# 1_-MCU_LPC1777.net
KiCad netlist of a schematic drawn in Altium Designer
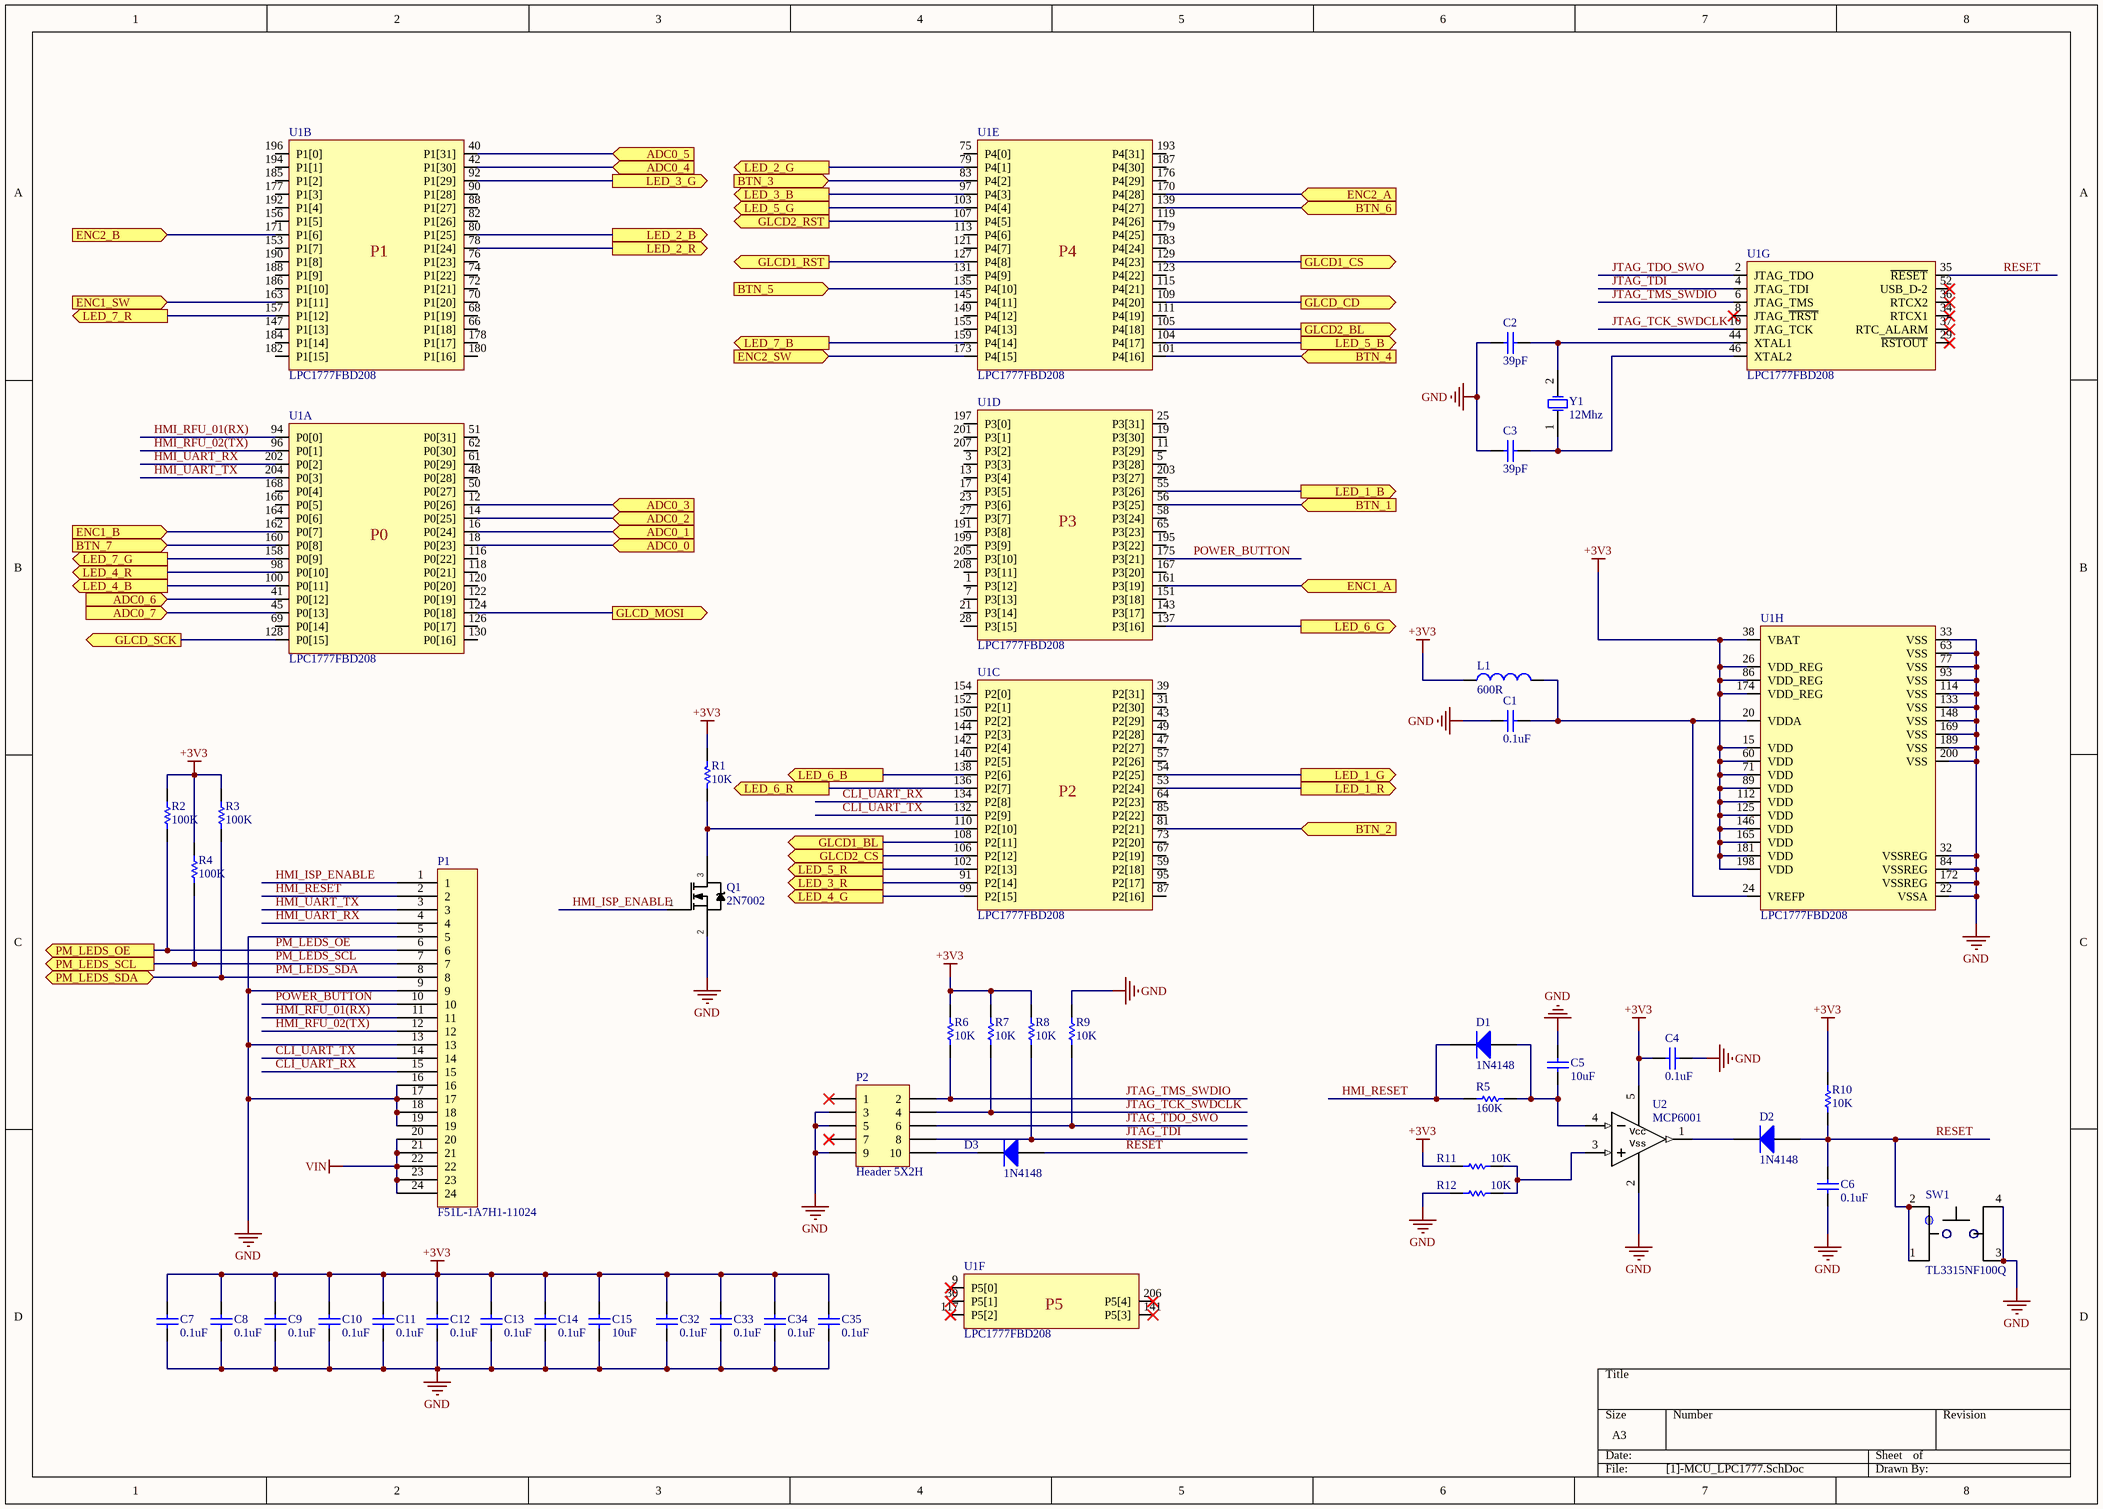
[diagram p0: [1]-MCU_LPC1777.SchDoc]

(export (version "E")
  (design (tool "Eeschema 10.0.6"))
  (components
    (comp (ref "C1")
      (value "0.1uF")
      (footprint "CAPC1005N")
      (description "CAP CER 0.1UF 50V X7R 0402")
      (fields (field (name "TOLERANCE") "10 %"))
      (libsource (lib "bitsnio") (part "GRM155R71H104KE14D"))
    )
    (comp (ref "C2")
      (value "39pF")
      (footprint "CAPC1608N")
      (description "CAP CER 39PF 50V NP0 0603")
      (fields (field (name "TOLERANCE") "5%"))
      (libsource (lib "bitsnio") (part "C1608NP01H390J080AA"))
    )
    (comp (ref "C3")
      (value "39pF")
      (footprint "CAPC1608N")
      (description "CAP CER 39PF 50V NP0 0603")
      (fields (field (name "TOLERANCE") "5%"))
      (libsource (lib "bitsnio") (part "C1608NP01H390J080AA"))
    )
    (comp (ref "C4")
      (value "0.1uF")
      (footprint "CAPC1608N")
      (description "CAP CER 0.1UF 25V X7R 0603")
      (fields (field (name "TOLERANCE") "10%") (field (name "VOLTAGE") "25V"))
      (libsource (lib "bitsnio") (part "CC0603KRX7R8BB104"))
    )
    (comp (ref "C5")
      (value "10uF")
      (footprint "CAPC1608N")
      (description "CAP CER 10UF 10V X5R 0603")
      (fields (field (name "TOLERANCE") "10%") (field (name "VOLTAGE") "10V"))
      (libsource (lib "bitsnio") (part "GRM188R61A106KE69D"))
    )
    (comp (ref "C6")
      (value "0.1uF")
      (footprint "CAPC1608N")
      (description "CAP CER 0.1UF 25V X7R 0603")
      (fields (field (name "TOLERANCE") "10%") (field (name "VOLTAGE") "25V"))
      (libsource (lib "bitsnio") (part "CC0603KRX7R8BB104"))
    )
    (comp (ref "C7")
      (value "0.1uF")
      (footprint "CAPC1005N")
      (description "CAP CER 0.1UF 50V X7R 0402")
      (fields (field (name "TOLERANCE") "10 %"))
      (libsource (lib "bitsnio") (part "GRM155R71H104KE14D"))
    )
    (comp (ref "C8")
      (value "0.1uF")
      (footprint "CAPC1005N")
      (description "CAP CER 0.1UF 50V X7R 0402")
      (fields (field (name "TOLERANCE") "10 %"))
      (libsource (lib "bitsnio") (part "GRM155R71H104KE14D"))
    )
    (comp (ref "C9")
      (value "0.1uF")
      (footprint "CAPC1005N")
      (description "CAP CER 0.1UF 50V X7R 0402")
      (fields (field (name "TOLERANCE") "10 %"))
      (libsource (lib "bitsnio") (part "GRM155R71H104KE14D"))
    )
    (comp (ref "C10")
      (value "0.1uF")
      (footprint "CAPC1005N")
      (description "CAP CER 0.1UF 50V X7R 0402")
      (fields (field (name "TOLERANCE") "10 %"))
      (libsource (lib "bitsnio") (part "GRM155R71H104KE14D"))
    )
    (comp (ref "C11")
      (value "0.1uF")
      (footprint "CAPC1005N")
      (description "CAP CER 0.1UF 50V X7R 0402")
      (fields (field (name "TOLERANCE") "10 %"))
      (libsource (lib "bitsnio") (part "GRM155R71H104KE14D"))
    )
    (comp (ref "C12")
      (value "0.1uF")
      (footprint "CAPC1005N")
      (description "CAP CER 0.1UF 50V X7R 0402")
      (fields (field (name "TOLERANCE") "10 %"))
      (libsource (lib "bitsnio") (part "GRM155R71H104KE14D"))
    )
    (comp (ref "C13")
      (value "0.1uF")
      (footprint "CAPC1005N")
      (description "CAP CER 0.1UF 50V X7R 0402")
      (fields (field (name "TOLERANCE") "10 %"))
      (libsource (lib "bitsnio") (part "GRM155R71H104KE14D"))
    )
    (comp (ref "C14")
      (value "0.1uF")
      (footprint "CAPC1005N")
      (description "CAP CER 0.1UF 50V X7R 0402")
      (fields (field (name "TOLERANCE") "10 %"))
      (libsource (lib "bitsnio") (part "GRM155R71H104KE14D"))
    )
    (comp (ref "C15")
      (value "10uF")
      (footprint "CAPC1608N")
      (description "CAP CER 10UF 10V X5R 0603")
      (fields (field (name "TOLERANCE") "10%") (field (name "VOLTAGE") "10V"))
      (libsource (lib "bitsnio") (part "GRM188R61A106KE69D"))
    )
    (comp (ref "C32")
      (value "0.1uF")
      (footprint "CAPC1005N")
      (description "CAP CER 0.1UF 50V X7R 0402")
      (fields (field (name "TOLERANCE") "10 %"))
      (libsource (lib "bitsnio") (part "GRM155R71H104KE14D"))
    )
    (comp (ref "C33")
      (value "0.1uF")
      (footprint "CAPC1005N")
      (description "CAP CER 0.1UF 50V X7R 0402")
      (fields (field (name "TOLERANCE") "10 %"))
      (libsource (lib "bitsnio") (part "GRM155R71H104KE14D"))
    )
    (comp (ref "C34")
      (value "0.1uF")
      (footprint "CAPC1005N")
      (description "CAP CER 0.1UF 50V X7R 0402")
      (fields (field (name "TOLERANCE") "10 %"))
      (libsource (lib "bitsnio") (part "GRM155R71H104KE14D"))
    )
    (comp (ref "C35")
      (value "0.1uF")
      (footprint "CAPC1005N")
      (description "CAP CER 0.1UF 50V X7R 0402")
      (fields (field (name "TOLERANCE") "10 %"))
      (libsource (lib "bitsnio") (part "GRM155R71H104KE14D"))
    )
    (comp (ref "D1")
      (value "1N4148")
      (footprint "SOD-323")
      (description "DIODE SWITCHING 75V 0.15A SOD323")
      (fields (field (name "VOLTAGE") "75V"))
      (libsource (lib "bitsnio") (part "1N4148WS-7-F"))
    )
    (comp (ref "D2")
      (value "1N4148")
      (footprint "SOD-323")
      (description "DIODE SWITCHING 75V 0.15A SOD323")
      (fields (field (name "VOLTAGE") "75V"))
      (libsource (lib "bitsnio") (part "1N4148WS-7-F"))
    )
    (comp (ref "D3")
      (value "1N4148")
      (footprint "SOD-323")
      (description "DIODE SWITCHING 75V 0.15A SOD323")
      (fields (field (name "VOLTAGE") "75V"))
      (libsource (lib "bitsnio") (part "1N4148WS-7-F"))
    )
    (comp (ref "L1")
      (value "600R")
      (footprint "INDC1608N")
      (description "FERRITE BEAD 600 OHM 1.0A 0603")
      (fields (field (name "TOLERANCE") "25%"))
      (libsource (lib "bitsnio") (part "742792651"))
    )
    (comp (ref "P1")
      (value "F51L-1A7H1-11024")
      (footprint "F51L-1A7H1-11024")
      (description "FLEX CONNECTOR, 1.00MM PITCH, HE")
      (libsource (lib "bitsnio") (part "F51L-1A7H1-11024"))
    )
    (comp (ref "P2")
      (value "Header 5X2H")
      (footprint "HDR2x5_1P27")
      (description "Header, 5-Pin, Dual row, Right Angle")
      (fields (field (name "PUBLISHER") "Altium Limited"))
      (libsource (lib "Miscellaneous Connectors") (part "Header 5X2H"))
    )
    (comp (ref "Q1")
      (value "2N7002")
      (footprint "SOT23-3N")
      (description "MOSFET N-CH 60V 115MA SOT-23")
      (fields (field (name "VOLTAGE") "60V"))
      (libsource (lib "bitsnio") (part "2N7002"))
    )
    (comp (ref "R1")
      (value "10K")
      (footprint "RESC1608N")
      (description "RES SMD 10K OHM 5% 1/10W 0603")
      (fields (field (name "TOLERANCE") "5%"))
      (libsource (lib "bitsnio") (part "AC0603JR-0710KL"))
    )
    (comp (ref "R2")
      (value "100K")
      (footprint "RESC1608N")
      (description "RES SMD 100K OHM 5% 1/4W 0603")
      (fields (field (name "TOLERANCE") "5%"))
      (libsource (lib "bitsnio") (part "ESR03EZPJ104"))
    )
    (comp (ref "R3")
      (value "100K")
      (footprint "RESC1608N")
      (description "RES SMD 100K OHM 5% 1/4W 0603")
      (fields (field (name "TOLERANCE") "5%"))
      (libsource (lib "bitsnio") (part "ESR03EZPJ104"))
    )
    (comp (ref "R4")
      (value "100K")
      (footprint "RESC1608N")
      (description "RES SMD 100K OHM 5% 1/4W 0603")
      (fields (field (name "TOLERANCE") "5%"))
      (libsource (lib "bitsnio") (part "ESR03EZPJ104"))
    )
    (comp (ref "R5")
      (value "160K")
      (footprint "RESC1608N")
      (description "RES SMD 160K OHM 5% 1/10W 0603")
      (fields (field (name "TOLERANCE") "5%"))
      (libsource (lib "bitsnio") (part "RMCF0603JT160K"))
    )
    (comp (ref "R6")
      (value "10K")
      (footprint "RESC1608N")
      (description "RES SMD 10K OHM 5% 1/10W 0603")
      (fields (field (name "TOLERANCE") "5%"))
      (libsource (lib "bitsnio") (part "AC0603JR-0710KL"))
    )
    (comp (ref "R7")
      (value "10K")
      (footprint "RESC1608N")
      (description "RES SMD 10K OHM 5% 1/10W 0603")
      (fields (field (name "TOLERANCE") "5%"))
      (libsource (lib "bitsnio") (part "AC0603JR-0710KL"))
    )
    (comp (ref "R8")
      (value "10K")
      (footprint "RESC1608N")
      (description "RES SMD 10K OHM 5% 1/10W 0603")
      (fields (field (name "TOLERANCE") "5%"))
      (libsource (lib "bitsnio") (part "AC0603JR-0710KL"))
    )
    (comp (ref "R9")
      (value "10K")
      (footprint "RESC1608N")
      (description "RES SMD 10K OHM 5% 1/10W 0603")
      (fields (field (name "TOLERANCE") "5%"))
      (libsource (lib "bitsnio") (part "AC0603JR-0710KL"))
    )
    (comp (ref "R10")
      (value "10K")
      (footprint "RESC1608N")
      (description "RES SMD 10K OHM 5% 1/10W 0603")
      (fields (field (name "TOLERANCE") "5%"))
      (libsource (lib "bitsnio") (part "AC0603JR-0710KL"))
    )
    (comp (ref "R11")
      (value "10K")
      (footprint "RESC1608N")
      (description "RES SMD 10K OHM 5% 1/10W 0603")
      (fields (field (name "TOLERANCE") "5%"))
      (libsource (lib "bitsnio") (part "AC0603JR-0710KL"))
    )
    (comp (ref "R12")
      (value "10K")
      (footprint "RESC1608N")
      (description "RES SMD 10K OHM 5% 1/10W 0603")
      (fields (field (name "TOLERANCE") "5%"))
      (libsource (lib "bitsnio") (part "AC0603JR-0710KL"))
    )
    (comp (ref "SW1")
      (value "TL3315NF100Q")
      (footprint "TL3315")
      (description "SWITCH TACTILE SPST-NO 0.05A 15V")
      (libsource (lib "bitsnio") (part "TL3315NF100Q"))
    )
    (comp (ref "U1")
      (value "LPC1777FBD208")
      (footprint "LQFP-208")
      (description "IC MCU 32BIT 512KB FLASH 208LQFP")
      (libsource (lib "bitsnio") (part "IC_LPC1777FBD208,551"))
    )
    (comp (ref "U2")
      (value "MCP6001")
      (footprint "SOT23-5N")
      (description "IC OPAMP GP 1MHZ RRO SOT23-5")
      (fields (field (name "VOLTAGE") "6V"))
      (libsource (lib "bitsnio") (part "IC_MCP6001T-I/OT"))
    )
    (comp (ref "Y1")
      (value "12Mhz")
      (footprint "CRYSTAL_HC49SDLF")
      (description "CRYSTAL 12.0000MHZ 20PF SMD")
      (libsource (lib "bitsnio") (part "FC4SDCBMF12.0-T1"))
    )
  )
  (nets
    (net (code "1") (name "+3V3") (class "Default")
      (node (ref "C10") (pin "2") (pinfunction "2_2") (pintype "passive"))
      (node (ref "C11") (pin "2") (pinfunction "2_2") (pintype "passive"))
      (node (ref "C12") (pin "2") (pinfunction "2_2") (pintype "passive"))
      (node (ref "C13") (pin "2") (pinfunction "2_2") (pintype "passive"))
      (node (ref "C14") (pin "2") (pinfunction "2_2") (pintype "passive"))
      (node (ref "C15") (pin "2") (pinfunction "2_2") (pintype "passive"))
      (node (ref "C32") (pin "2") (pinfunction "2_2") (pintype "passive"))
      (node (ref "C33") (pin "2") (pinfunction "2_2") (pintype "passive"))
      (node (ref "C34") (pin "2") (pinfunction "2_2") (pintype "passive"))
      (node (ref "C35") (pin "2") (pinfunction "2_2") (pintype "passive"))
      (node (ref "C4") (pin "2") (pinfunction "2_2") (pintype "passive"))
      (node (ref "C7") (pin "2") (pinfunction "2_2") (pintype "passive"))
      (node (ref "C8") (pin "2") (pinfunction "2_2") (pintype "passive"))
      (node (ref "C9") (pin "2") (pinfunction "2_2") (pintype "passive"))
      (node (ref "L1") (pin "2") (pinfunction "2_2") (pintype "passive"))
      (node (ref "R1") (pin "1") (pinfunction "1_1") (pintype "passive"))
      (node (ref "R10") (pin "1") (pinfunction "1_1") (pintype "passive"))
      (node (ref "R11") (pin "2") (pinfunction "2_2") (pintype "passive"))
      (node (ref "R2") (pin "2") (pinfunction "2_2") (pintype "passive"))
      (node (ref "R3") (pin "2") (pinfunction "2_2") (pintype "passive"))
      (node (ref "R4") (pin "2") (pinfunction "2_2") (pintype "passive"))
      (node (ref "R6") (pin "1") (pinfunction "1_1") (pintype "passive"))
      (node (ref "R7") (pin "1") (pinfunction "1_1") (pintype "passive"))
      (node (ref "R8") (pin "1") (pinfunction "1_1") (pintype "passive"))
      (node (ref "U1") (pin "112") (pinfunction "VDD_112") (pintype "passive"))
      (node (ref "U1") (pin "125") (pinfunction "VDD_125") (pintype "passive"))
      (node (ref "U1") (pin "146") (pinfunction "VDD_146") (pintype "passive"))
      (node (ref "U1") (pin "15") (pinfunction "VDD_15") (pintype "passive"))
      (node (ref "U1") (pin "165") (pinfunction "VDD_165") (pintype "passive"))
      (node (ref "U1") (pin "174") (pinfunction "VDD_REG_174") (pintype "passive"))
      (node (ref "U1") (pin "181") (pinfunction "VDD_181") (pintype "passive"))
      (node (ref "U1") (pin "198") (pinfunction "VDD_198") (pintype "passive"))
      (node (ref "U1") (pin "26") (pinfunction "VDD_REG_26") (pintype "passive"))
      (node (ref "U1") (pin "38") (pinfunction "VBAT_38") (pintype "passive"))
      (node (ref "U1") (pin "60") (pinfunction "VDD_60") (pintype "passive"))
      (node (ref "U1") (pin "71") (pinfunction "VDD_71") (pintype "passive"))
      (node (ref "U1") (pin "86") (pinfunction "VDD_REG_86") (pintype "passive"))
      (node (ref "U1") (pin "89") (pinfunction "VDD_89") (pintype "passive"))
      (node (ref "U2") (pin "5") (pinfunction "VCC_5") (pintype "power_in"))
    )
    (net (code "2") (name "/ADC0_0") (class "Default")
      (node (ref "U1") (pin "18") (pinfunction "P0[23]_18") (pintype "passive"))
    )
    (net (code "3") (name "/ADC0_1") (class "Default")
      (node (ref "U1") (pin "16") (pinfunction "P0[24]_16") (pintype "passive"))
    )
    (net (code "4") (name "/ADC0_2") (class "Default")
      (node (ref "U1") (pin "14") (pinfunction "P0[25]_14") (pintype "passive"))
    )
    (net (code "5") (name "/ADC0_3") (class "Default")
      (node (ref "U1") (pin "12") (pinfunction "P0[26]_12") (pintype "passive"))
    )
    (net (code "6") (name "/ADC0_4") (class "Default")
      (node (ref "U1") (pin "42") (pinfunction "P1[30]_42") (pintype "passive"))
    )
    (net (code "7") (name "/ADC0_5") (class "Default")
      (node (ref "U1") (pin "40") (pinfunction "P1[31]_40") (pintype "passive"))
    )
    (net (code "8") (name "/ADC0_6") (class "Default")
      (node (ref "U1") (pin "41") (pinfunction "P0[12]_41") (pintype "passive"))
    )
    (net (code "9") (name "/ADC0_7") (class "Default")
      (node (ref "U1") (pin "45") (pinfunction "P0[13]_45") (pintype "passive"))
    )
    (net (code "10") (name "/BTN_1") (class "Default")
      (node (ref "U1") (pin "56") (pinfunction "P3[25]_56") (pintype "passive"))
    )
    (net (code "11") (name "/BTN_2") (class "Default")
      (node (ref "U1") (pin "81") (pinfunction "P2[21]_81") (pintype "passive"))
    )
    (net (code "12") (name "/BTN_3") (class "Default")
      (node (ref "U1") (pin "83") (pinfunction "P4[2]_83") (pintype "passive"))
    )
    (net (code "13") (name "/BTN_4") (class "Default")
      (node (ref "U1") (pin "101") (pinfunction "P4[16]_101") (pintype "passive"))
    )
    (net (code "14") (name "/BTN_5") (class "Default")
      (node (ref "U1") (pin "135") (pinfunction "P4[10]_135") (pintype "passive"))
    )
    (net (code "15") (name "/BTN_6") (class "Default")
      (node (ref "U1") (pin "139") (pinfunction "P4[27]_139") (pintype "passive"))
    )
    (net (code "16") (name "/BTN_7") (class "Default")
      (node (ref "U1") (pin "160") (pinfunction "P0[8]_160") (pintype "passive"))
    )
    (net (code "17") (name "/CLI_UART_RX") (class "Default")
      (node (ref "P1") (pin "15") (pinfunction "15_15") (pintype "passive"))
      (node (ref "U1") (pin "134") (pinfunction "P2[8]_134") (pintype "passive"))
    )
    (net (code "18") (name "/CLI_UART_TX") (class "Default")
      (node (ref "P1") (pin "14") (pinfunction "14_14") (pintype "passive"))
      (node (ref "U1") (pin "132") (pinfunction "P2[9]_132") (pintype "passive"))
    )
    (net (code "19") (name "/ENC1_A") (class "Default")
      (node (ref "U1") (pin "161") (pinfunction "P3[19]_161") (pintype "passive"))
    )
    (net (code "20") (name "/ENC1_B") (class "Default")
      (node (ref "U1") (pin "162") (pinfunction "P0[7]_162") (pintype "passive"))
    )
    (net (code "21") (name "/ENC1_SW") (class "Default")
      (node (ref "U1") (pin "163") (pinfunction "P1[11]_163") (pintype "passive"))
    )
    (net (code "22") (name "/ENC2_A") (class "Default")
      (node (ref "U1") (pin "170") (pinfunction "P4[28]_170") (pintype "passive"))
    )
    (net (code "23") (name "/ENC2_B") (class "Default")
      (node (ref "U1") (pin "171") (pinfunction "P1[6]_171") (pintype "passive"))
    )
    (net (code "24") (name "/ENC2_SW") (class "Default")
      (node (ref "U1") (pin "173") (pinfunction "P4[15]_173") (pintype "passive"))
    )
    (net (code "25") (name "/GLCD1_BL") (class "Default")
      (node (ref "U1") (pin "108") (pinfunction "P2[11]_108") (pintype "passive"))
    )
    (net (code "26") (name "/GLCD1_CS") (class "Default")
      (node (ref "U1") (pin "129") (pinfunction "P4[23]_129") (pintype "passive"))
    )
    (net (code "27") (name "/GLCD1_RST") (class "Default")
      (node (ref "U1") (pin "127") (pinfunction "P4[8]_127") (pintype "passive"))
    )
    (net (code "28") (name "/GLCD2_BL") (class "Default")
      (node (ref "U1") (pin "105") (pinfunction "P4[18]_105") (pintype "passive"))
    )
    (net (code "29") (name "/GLCD2_CS") (class "Default")
      (node (ref "U1") (pin "106") (pinfunction "P2[12]_106") (pintype "passive"))
    )
    (net (code "30") (name "/GLCD2_RST") (class "Default")
      (node (ref "U1") (pin "107") (pinfunction "P4[5]_107") (pintype "passive"))
    )
    (net (code "31") (name "/GLCD_CD") (class "Default")
      (node (ref "U1") (pin "109") (pinfunction "P4[20]_109") (pintype "passive"))
    )
    (net (code "32") (name "/GLCD_MOSI") (class "Default")
      (node (ref "U1") (pin "124") (pinfunction "P0[18]_124") (pintype "passive"))
    )
    (net (code "33") (name "/GLCD_SCK") (class "Default")
      (node (ref "U1") (pin "128") (pinfunction "P0[15]_128") (pintype "passive"))
    )
    (net (code "34") (name "/HMI_ISP_ENABLE") (class "Default")
      (node (ref "P1") (pin "1") (pinfunction "1_1") (pintype "passive"))
      (node (ref "Q1") (pin "1") (pinfunction "G_1") (pintype "passive"))
    )
    (net (code "35") (name "/HMI_RESET") (class "Default")
      (node (ref "D1") (pin "1") (pinfunction "K_1") (pintype "passive"))
      (node (ref "P1") (pin "2") (pinfunction "2_2") (pintype "passive"))
      (node (ref "R5") (pin "1") (pinfunction "1_1") (pintype "passive"))
    )
    (net (code "36") (name "/HMI_RFU_01(RX)") (class "Default")
      (node (ref "P1") (pin "11") (pinfunction "11_11") (pintype "passive"))
      (node (ref "U1") (pin "94") (pinfunction "P0[0]_94") (pintype "passive"))
    )
    (net (code "37") (name "/HMI_RFU_02(TX)") (class "Default")
      (node (ref "P1") (pin "12") (pinfunction "12_12") (pintype "passive"))
      (node (ref "U1") (pin "96") (pinfunction "P0[1]_96") (pintype "passive"))
    )
    (net (code "38") (name "/HMI_UART_RX") (class "Default")
      (node (ref "P1") (pin "4") (pinfunction "4_4") (pintype "passive"))
      (node (ref "U1") (pin "202") (pinfunction "P0[2]_202") (pintype "passive"))
    )
    (net (code "39") (name "/HMI_UART_TX") (class "Default")
      (node (ref "P1") (pin "3") (pinfunction "3_3") (pintype "passive"))
      (node (ref "U1") (pin "204") (pinfunction "P0[3]_204") (pintype "passive"))
    )
    (net (code "40") (name "/JTAG_TCK_SWDCLK") (class "Default")
      (node (ref "P2") (pin "4") (pinfunction "4_4") (pintype "passive"))
      (node (ref "R7") (pin "2") (pinfunction "2_2") (pintype "passive"))
      (node (ref "U1") (pin "10") (pinfunction "JTAG_TCK_10") (pintype "passive"))
    )
    (net (code "41") (name "/JTAG_TDI") (class "Default")
      (node (ref "P2") (pin "8") (pinfunction "8_8") (pintype "passive"))
      (node (ref "R8") (pin "2") (pinfunction "2_2") (pintype "passive"))
      (node (ref "U1") (pin "4") (pinfunction "JTAG_TDI_4") (pintype "passive"))
    )
    (net (code "42") (name "/JTAG_TDO_SWO") (class "Default")
      (node (ref "P2") (pin "6") (pinfunction "6_6") (pintype "passive"))
      (node (ref "R9") (pin "2") (pinfunction "2_2") (pintype "passive"))
      (node (ref "U1") (pin "2") (pinfunction "JTAG_TDO_2") (pintype "passive"))
    )
    (net (code "43") (name "/JTAG_TMS_SWDIO") (class "Default")
      (node (ref "P2") (pin "2") (pinfunction "2_2") (pintype "passive"))
      (node (ref "R6") (pin "2") (pinfunction "2_2") (pintype "passive"))
      (node (ref "U1") (pin "6") (pinfunction "JTAG_TMS_6") (pintype "passive"))
    )
    (net (code "44") (name "/LED_1_B") (class "Default")
      (node (ref "U1") (pin "55") (pinfunction "P3[26]_55") (pintype "passive"))
    )
    (net (code "45") (name "/LED_1_G") (class "Default")
      (node (ref "U1") (pin "54") (pinfunction "P2[25]_54") (pintype "passive"))
    )
    (net (code "46") (name "/LED_1_R") (class "Default")
      (node (ref "U1") (pin "53") (pinfunction "P2[24]_53") (pintype "passive"))
    )
    (net (code "47") (name "/LED_2_B") (class "Default")
      (node (ref "U1") (pin "80") (pinfunction "P1[25]_80") (pintype "passive"))
    )
    (net (code "48") (name "/LED_2_G") (class "Default")
      (node (ref "U1") (pin "79") (pinfunction "P4[1]_79") (pintype "passive"))
    )
    (net (code "49") (name "/LED_2_R") (class "Default")
      (node (ref "U1") (pin "78") (pinfunction "P1[24]_78") (pintype "passive"))
    )
    (net (code "50") (name "/LED_3_B") (class "Default")
      (node (ref "U1") (pin "97") (pinfunction "P4[3]_97") (pintype "passive"))
    )
    (net (code "51") (name "/LED_3_G") (class "Default")
      (node (ref "U1") (pin "92") (pinfunction "P1[29]_92") (pintype "passive"))
    )
    (net (code "52") (name "/LED_3_R") (class "Default")
      (node (ref "U1") (pin "91") (pinfunction "P2[14]_91") (pintype "passive"))
    )
    (net (code "53") (name "/LED_4_B") (class "Default")
      (node (ref "U1") (pin "100") (pinfunction "P0[11]_100") (pintype "passive"))
    )
    (net (code "54") (name "/LED_4_G") (class "Default")
      (node (ref "U1") (pin "99") (pinfunction "P2[15]_99") (pintype "passive"))
    )
    (net (code "55") (name "/LED_4_R") (class "Default")
      (node (ref "U1") (pin "98") (pinfunction "P0[10]_98") (pintype "passive"))
    )
    (net (code "56") (name "/LED_5_B") (class "Default")
      (node (ref "U1") (pin "104") (pinfunction "P4[17]_104") (pintype "passive"))
    )
    (net (code "57") (name "/LED_5_G") (class "Default")
      (node (ref "U1") (pin "103") (pinfunction "P4[4]_103") (pintype "passive"))
    )
    (net (code "58") (name "/LED_5_R") (class "Default")
      (node (ref "U1") (pin "102") (pinfunction "P2[13]_102") (pintype "passive"))
    )
    (net (code "59") (name "/LED_6_B") (class "Default")
      (node (ref "U1") (pin "138") (pinfunction "P2[6]_138") (pintype "passive"))
    )
    (net (code "60") (name "/LED_6_G") (class "Default")
      (node (ref "U1") (pin "137") (pinfunction "P3[16]_137") (pintype "passive"))
    )
    (net (code "61") (name "/LED_6_R") (class "Default")
      (node (ref "U1") (pin "136") (pinfunction "P2[7]_136") (pintype "passive"))
    )
    (net (code "62") (name "/LED_7_B") (class "Default")
      (node (ref "U1") (pin "159") (pinfunction "P4[14]_159") (pintype "passive"))
    )
    (net (code "63") (name "/LED_7_G") (class "Default")
      (node (ref "U1") (pin "158") (pinfunction "P0[9]_158") (pintype "passive"))
    )
    (net (code "64") (name "/LED_7_R") (class "Default")
      (node (ref "U1") (pin "157") (pinfunction "P1[12]_157") (pintype "passive"))
    )
    (net (code "65") (name "/PM_LEDS_OE") (class "Default")
      (node (ref "P1") (pin "6") (pinfunction "6_6") (pintype "passive"))
      (node (ref "R2") (pin "1") (pinfunction "1_1") (pintype "passive"))
    )
    (net (code "66") (name "/PM_LEDS_SCL") (class "Default")
      (node (ref "P1") (pin "7") (pinfunction "7_7") (pintype "passive"))
      (node (ref "R4") (pin "1") (pinfunction "1_1") (pintype "passive"))
    )
    (net (code "67") (name "/PM_LEDS_SDA") (class "Default")
      (node (ref "P1") (pin "8") (pinfunction "8_8") (pintype "passive"))
      (node (ref "R3") (pin "1") (pinfunction "1_1") (pintype "passive"))
    )
    (net (code "68") (name "/POWER_BUTTON") (class "Default")
      (node (ref "P1") (pin "10") (pinfunction "10_10") (pintype "passive"))
      (node (ref "U1") (pin "175") (pinfunction "P3[21]_175") (pintype "passive"))
    )
    (net (code "69") (name "/RESET") (class "Default")
      (node (ref "C6") (pin "1") (pinfunction "1_1") (pintype "passive"))
      (node (ref "D2") (pin "2") (pinfunction "A_2") (pintype "passive"))
      (node (ref "D3") (pin "2") (pinfunction "A_2") (pintype "passive"))
      (node (ref "R10") (pin "2") (pinfunction "2_2") (pintype "passive"))
      (node (ref "SW1") (pin "1") (pinfunction "1_1") (pintype "passive"))
      (node (ref "SW1") (pin "2") (pinfunction "2_2") (pintype "passive"))
      (node (ref "U1") (pin "35") (pinfunction "~{RESET}_35") (pintype "passive"))
    )
    (net (code "70") (name "GND") (class "Default")
      (node (ref "C1") (pin "2") (pinfunction "2_2") (pintype "passive"))
      (node (ref "C10") (pin "1") (pinfunction "1_1") (pintype "passive"))
      (node (ref "C11") (pin "1") (pinfunction "1_1") (pintype "passive"))
      (node (ref "C12") (pin "1") (pinfunction "1_1") (pintype "passive"))
      (node (ref "C13") (pin "1") (pinfunction "1_1") (pintype "passive"))
      (node (ref "C14") (pin "1") (pinfunction "1_1") (pintype "passive"))
      (node (ref "C15") (pin "1") (pinfunction "1_1") (pintype "passive"))
      (node (ref "C2") (pin "2") (pinfunction "2_2") (pintype "passive"))
      (node (ref "C3") (pin "1") (pinfunction "1_1") (pintype "passive"))
      (node (ref "C32") (pin "1") (pinfunction "1_1") (pintype "passive"))
      (node (ref "C33") (pin "1") (pinfunction "1_1") (pintype "passive"))
      (node (ref "C34") (pin "1") (pinfunction "1_1") (pintype "passive"))
      (node (ref "C35") (pin "1") (pinfunction "1_1") (pintype "passive"))
      (node (ref "C4") (pin "1") (pinfunction "1_1") (pintype "passive"))
      (node (ref "C5") (pin "1") (pinfunction "1_1") (pintype "passive"))
      (node (ref "C6") (pin "2") (pinfunction "2_2") (pintype "passive"))
      (node (ref "C7") (pin "1") (pinfunction "1_1") (pintype "passive"))
      (node (ref "C8") (pin "1") (pinfunction "1_1") (pintype "passive"))
      (node (ref "C9") (pin "1") (pinfunction "1_1") (pintype "passive"))
      (node (ref "P1") (pin "13") (pinfunction "13_13") (pintype "passive"))
      (node (ref "P1") (pin "16") (pinfunction "16_16") (pintype "passive"))
      (node (ref "P1") (pin "17") (pinfunction "17_17") (pintype "passive"))
      (node (ref "P1") (pin "18") (pinfunction "18_18") (pintype "passive"))
      (node (ref "P1") (pin "19") (pinfunction "19_19") (pintype "passive"))
      (node (ref "P1") (pin "5") (pinfunction "5_5") (pintype "passive"))
      (node (ref "P1") (pin "9") (pinfunction "9_9") (pintype "passive"))
      (node (ref "P2") (pin "3") (pinfunction "3_3") (pintype "passive"))
      (node (ref "P2") (pin "5") (pinfunction "5_5") (pintype "passive"))
      (node (ref "P2") (pin "9") (pinfunction "9_9") (pintype "passive"))
      (node (ref "Q1") (pin "2") (pinfunction "S_2") (pintype "passive"))
      (node (ref "R12") (pin "2") (pinfunction "2_2") (pintype "passive"))
      (node (ref "R9") (pin "1") (pinfunction "1_1") (pintype "passive"))
      (node (ref "SW1") (pin "3") (pinfunction "3_3") (pintype "passive"))
      (node (ref "SW1") (pin "4") (pinfunction "4_4") (pintype "passive"))
      (node (ref "U1") (pin "114") (pinfunction "VSS_114") (pintype "passive"))
      (node (ref "U1") (pin "133") (pinfunction "VSS_133") (pintype "passive"))
      (node (ref "U1") (pin "148") (pinfunction "VSS_148") (pintype "passive"))
      (node (ref "U1") (pin "169") (pinfunction "VSS_169") (pintype "passive"))
      (node (ref "U1") (pin "172") (pinfunction "VSSREG_172") (pintype "passive"))
      (node (ref "U1") (pin "189") (pinfunction "VSS_189") (pintype "passive"))
      (node (ref "U1") (pin "200") (pinfunction "VSS_200") (pintype "passive"))
      (node (ref "U1") (pin "22") (pinfunction "VSSA_22") (pintype "passive"))
      (node (ref "U1") (pin "32") (pinfunction "VSSREG_32") (pintype "passive"))
      (node (ref "U1") (pin "33") (pinfunction "VSS_33") (pintype "passive"))
      (node (ref "U1") (pin "63") (pinfunction "VSS_63") (pintype "passive"))
      (node (ref "U1") (pin "77") (pinfunction "VSS_77") (pintype "passive"))
      (node (ref "U1") (pin "84") (pinfunction "VSSREG_84") (pintype "passive"))
      (node (ref "U1") (pin "93") (pinfunction "VSS_93") (pintype "passive"))
      (node (ref "U2") (pin "2") (pinfunction "VSS_2") (pintype "power_in"))
    )
    (net (code "71") (name "Net-(D1-A)") (class "Default")
      (node (ref "C5") (pin "2") (pinfunction "2_2") (pintype "passive"))
      (node (ref "D1") (pin "2") (pinfunction "A_2") (pintype "passive"))
      (node (ref "R5") (pin "2") (pinfunction "2_2") (pintype "passive"))
      (node (ref "U2") (pin "4") (pinfunction "IN-_4") (pintype "input"))
    )
    (net (code "72") (name "Net-(D2-K)") (class "Default")
      (node (ref "D2") (pin "1") (pinfunction "K_1") (pintype "passive"))
      (node (ref "U2") (pin "1") (pinfunction "OUT_1") (pintype "output"))
    )
    (net (code "73") (name "Net-(D3-K)") (class "Default")
      (node (ref "D3") (pin "1") (pinfunction "K_1") (pintype "passive"))
      (node (ref "P2") (pin "10") (pinfunction "10_10") (pintype "passive"))
    )
    (net (code "74") (name "Net-(Q1-D)") (class "Default")
      (node (ref "Q1") (pin "3") (pinfunction "D_3") (pintype "passive"))
      (node (ref "R1") (pin "2") (pinfunction "2_2") (pintype "passive"))
      (node (ref "U1") (pin "110") (pinfunction "P2[10]_110") (pintype "passive"))
    )
    (net (code "75") (name "Net-(U1G-XTAL1)") (class "Default")
      (node (ref "C2") (pin "1") (pinfunction "1_1") (pintype "passive"))
      (node (ref "U1") (pin "44") (pinfunction "XTAL1_44") (pintype "passive"))
      (node (ref "Y1") (pin "2") (pinfunction "OSC2_2") (pintype "passive"))
    )
    (net (code "76") (name "Net-(U1G-XTAL2)") (class "Default")
      (node (ref "C3") (pin "2") (pinfunction "2_2") (pintype "passive"))
      (node (ref "U1") (pin "46") (pinfunction "XTAL2_46") (pintype "passive"))
      (node (ref "Y1") (pin "1") (pinfunction "OSC1_1") (pintype "passive"))
    )
    (net (code "77") (name "Net-(U1H-VDDA)") (class "Default")
      (node (ref "C1") (pin "1") (pinfunction "1_1") (pintype "passive"))
      (node (ref "L1") (pin "1") (pinfunction "1_1") (pintype "passive"))
      (node (ref "U1") (pin "20") (pinfunction "VDDA_20") (pintype "passive"))
      (node (ref "U1") (pin "24") (pinfunction "VREFP_24") (pintype "passive"))
    )
    (net (code "78") (name "Net-(U2-IN+)") (class "Default")
      (node (ref "R11") (pin "1") (pinfunction "1_1") (pintype "passive"))
      (node (ref "R12") (pin "1") (pinfunction "1_1") (pintype "passive"))
      (node (ref "U2") (pin "3") (pinfunction "IN+_3") (pintype "input"))
    )
    (net (code "79") (name "VIN") (class "Default")
      (node (ref "P1") (pin "20") (pinfunction "20_20") (pintype "passive"))
      (node (ref "P1") (pin "21") (pinfunction "21_21") (pintype "passive"))
      (node (ref "P1") (pin "22") (pinfunction "22_22") (pintype "passive"))
      (node (ref "P1") (pin "23") (pinfunction "23_23") (pintype "passive"))
      (node (ref "P1") (pin "24") (pinfunction "24_24") (pintype "passive"))
    )
    (net (code "80") (name "unconnected-(P2-Pad1)") (class "Default")
      (node (ref "P2") (pin "1") (pinfunction "1_1") (pintype "passive+no_connect"))
    )
    (net (code "81") (name "unconnected-(P2-Pad7)") (class "Default")
      (node (ref "P2") (pin "7") (pinfunction "7_7") (pintype "passive+no_connect"))
    )
    (net (code "82") (name "unconnected-(U1A-P0[4]-Pad168)") (class "Default")
      (node (ref "U1") (pin "168") (pinfunction "P0[4]_168") (pintype "passive"))
    )
    (net (code "83") (name "unconnected-(U1A-P0[5]-Pad166)") (class "Default")
      (node (ref "U1") (pin "166") (pinfunction "P0[5]_166") (pintype "passive"))
    )
    (net (code "84") (name "unconnected-(U1A-P0[6]-Pad164)") (class "Default")
      (node (ref "U1") (pin "164") (pinfunction "P0[6]_164") (pintype "passive"))
    )
    (net (code "85") (name "unconnected-(U1A-P0[14]-Pad69)") (class "Default")
      (node (ref "U1") (pin "69") (pinfunction "P0[14]_69") (pintype "passive"))
    )
    (net (code "86") (name "unconnected-(U1A-P0[16]-Pad130)") (class "Default")
      (node (ref "U1") (pin "130") (pinfunction "P0[16]_130") (pintype "passive"))
    )
    (net (code "87") (name "unconnected-(U1A-P0[17]-Pad126)") (class "Default")
      (node (ref "U1") (pin "126") (pinfunction "P0[17]_126") (pintype "passive"))
    )
    (net (code "88") (name "unconnected-(U1A-P0[19]-Pad122)") (class "Default")
      (node (ref "U1") (pin "122") (pinfunction "P0[19]_122") (pintype "passive"))
    )
    (net (code "89") (name "unconnected-(U1A-P0[20]-Pad120)") (class "Default")
      (node (ref "U1") (pin "120") (pinfunction "P0[20]_120") (pintype "passive"))
    )
    (net (code "90") (name "unconnected-(U1A-P0[21]-Pad118)") (class "Default")
      (node (ref "U1") (pin "118") (pinfunction "P0[21]_118") (pintype "passive"))
    )
    (net (code "91") (name "unconnected-(U1A-P0[22]-Pad116)") (class "Default")
      (node (ref "U1") (pin "116") (pinfunction "P0[22]_116") (pintype "passive"))
    )
    (net (code "92") (name "unconnected-(U1A-P0[27]-Pad50)") (class "Default")
      (node (ref "U1") (pin "50") (pinfunction "P0[27]_50") (pintype "passive"))
    )
    (net (code "93") (name "unconnected-(U1A-P0[28]-Pad48)") (class "Default")
      (node (ref "U1") (pin "48") (pinfunction "P0[28]_48") (pintype "passive"))
    )
    (net (code "94") (name "unconnected-(U1A-P0[29]-Pad61)") (class "Default")
      (node (ref "U1") (pin "61") (pinfunction "P0[29]_61") (pintype "passive"))
    )
    (net (code "95") (name "unconnected-(U1A-P0[30]-Pad62)") (class "Default")
      (node (ref "U1") (pin "62") (pinfunction "P0[30]_62") (pintype "passive"))
    )
    (net (code "96") (name "unconnected-(U1A-P0[31]-Pad51)") (class "Default")
      (node (ref "U1") (pin "51") (pinfunction "P0[31]_51") (pintype "passive"))
    )
    (net (code "97") (name "unconnected-(U1B-P1[0]-Pad196)") (class "Default")
      (node (ref "U1") (pin "196") (pinfunction "P1[0]_196") (pintype "passive"))
    )
    (net (code "98") (name "unconnected-(U1B-P1[1]-Pad194)") (class "Default")
      (node (ref "U1") (pin "194") (pinfunction "P1[1]_194") (pintype "passive"))
    )
    (net (code "99") (name "unconnected-(U1B-P1[2]-Pad185)") (class "Default")
      (node (ref "U1") (pin "185") (pinfunction "P1[2]_185") (pintype "passive"))
    )
    (net (code "100") (name "unconnected-(U1B-P1[3]-Pad177)") (class "Default")
      (node (ref "U1") (pin "177") (pinfunction "P1[3]_177") (pintype "passive"))
    )
    (net (code "101") (name "unconnected-(U1B-P1[4]-Pad192)") (class "Default")
      (node (ref "U1") (pin "192") (pinfunction "P1[4]_192") (pintype "passive"))
    )
    (net (code "102") (name "unconnected-(U1B-P1[5]-Pad156)") (class "Default")
      (node (ref "U1") (pin "156") (pinfunction "P1[5]_156") (pintype "passive"))
    )
    (net (code "103") (name "unconnected-(U1B-P1[7]-Pad153)") (class "Default")
      (node (ref "U1") (pin "153") (pinfunction "P1[7]_153") (pintype "passive"))
    )
    (net (code "104") (name "unconnected-(U1B-P1[8]-Pad190)") (class "Default")
      (node (ref "U1") (pin "190") (pinfunction "P1[8]_190") (pintype "passive"))
    )
    (net (code "105") (name "unconnected-(U1B-P1[9]-Pad188)") (class "Default")
      (node (ref "U1") (pin "188") (pinfunction "P1[9]_188") (pintype "passive"))
    )
    (net (code "106") (name "unconnected-(U1B-P1[10]-Pad186)") (class "Default")
      (node (ref "U1") (pin "186") (pinfunction "P1[10]_186") (pintype "passive"))
    )
    (net (code "107") (name "unconnected-(U1B-P1[13]-Pad147)") (class "Default")
      (node (ref "U1") (pin "147") (pinfunction "P1[13]_147") (pintype "passive"))
    )
    (net (code "108") (name "unconnected-(U1B-P1[14]-Pad184)") (class "Default")
      (node (ref "U1") (pin "184") (pinfunction "P1[14]_184") (pintype "passive"))
    )
    (net (code "109") (name "unconnected-(U1B-P1[15]-Pad182)") (class "Default")
      (node (ref "U1") (pin "182") (pinfunction "P1[15]_182") (pintype "passive"))
    )
    (net (code "110") (name "unconnected-(U1B-P1[16]-Pad180)") (class "Default")
      (node (ref "U1") (pin "180") (pinfunction "P1[16]_180") (pintype "passive"))
    )
    (net (code "111") (name "unconnected-(U1B-P1[17]-Pad178)") (class "Default")
      (node (ref "U1") (pin "178") (pinfunction "P1[17]_178") (pintype "passive"))
    )
    (net (code "112") (name "unconnected-(U1B-P1[18]-Pad66)") (class "Default")
      (node (ref "U1") (pin "66") (pinfunction "P1[18]_66") (pintype "passive"))
    )
    (net (code "113") (name "unconnected-(U1B-P1[19]-Pad68)") (class "Default")
      (node (ref "U1") (pin "68") (pinfunction "P1[19]_68") (pintype "passive"))
    )
    (net (code "114") (name "unconnected-(U1B-P1[20]-Pad70)") (class "Default")
      (node (ref "U1") (pin "70") (pinfunction "P1[20]_70") (pintype "passive"))
    )
    (net (code "115") (name "unconnected-(U1B-P1[21]-Pad72)") (class "Default")
      (node (ref "U1") (pin "72") (pinfunction "P1[21]_72") (pintype "passive"))
    )
    (net (code "116") (name "unconnected-(U1B-P1[22]-Pad74)") (class "Default")
      (node (ref "U1") (pin "74") (pinfunction "P1[22]_74") (pintype "passive"))
    )
    (net (code "117") (name "unconnected-(U1B-P1[23]-Pad76)") (class "Default")
      (node (ref "U1") (pin "76") (pinfunction "P1[23]_76") (pintype "passive"))
    )
    (net (code "118") (name "unconnected-(U1B-P1[26]-Pad82)") (class "Default")
      (node (ref "U1") (pin "82") (pinfunction "P1[26]_82") (pintype "passive"))
    )
    (net (code "119") (name "unconnected-(U1B-P1[27]-Pad88)") (class "Default")
      (node (ref "U1") (pin "88") (pinfunction "P1[27]_88") (pintype "passive"))
    )
    (net (code "120") (name "unconnected-(U1B-P1[28]-Pad90)") (class "Default")
      (node (ref "U1") (pin "90") (pinfunction "P1[28]_90") (pintype "passive"))
    )
    (net (code "121") (name "unconnected-(U1C-P2[0]-Pad154)") (class "Default")
      (node (ref "U1") (pin "154") (pinfunction "P2[0]_154") (pintype "passive"))
    )
    (net (code "122") (name "unconnected-(U1C-P2[1]-Pad152)") (class "Default")
      (node (ref "U1") (pin "152") (pinfunction "P2[1]_152") (pintype "passive"))
    )
    (net (code "123") (name "unconnected-(U1C-P2[2]-Pad150)") (class "Default")
      (node (ref "U1") (pin "150") (pinfunction "P2[2]_150") (pintype "passive"))
    )
    (net (code "124") (name "unconnected-(U1C-P2[3]-Pad144)") (class "Default")
      (node (ref "U1") (pin "144") (pinfunction "P2[3]_144") (pintype "passive"))
    )
    (net (code "125") (name "unconnected-(U1C-P2[4]-Pad142)") (class "Default")
      (node (ref "U1") (pin "142") (pinfunction "P2[4]_142") (pintype "passive"))
    )
    (net (code "126") (name "unconnected-(U1C-P2[5]-Pad140)") (class "Default")
      (node (ref "U1") (pin "140") (pinfunction "P2[5]_140") (pintype "passive"))
    )
    (net (code "127") (name "unconnected-(U1C-P2[16]-Pad87)") (class "Default")
      (node (ref "U1") (pin "87") (pinfunction "P2[16]_87") (pintype "passive"))
    )
    (net (code "128") (name "unconnected-(U1C-P2[17]-Pad95)") (class "Default")
      (node (ref "U1") (pin "95") (pinfunction "P2[17]_95") (pintype "passive"))
    )
    (net (code "129") (name "unconnected-(U1C-P2[18]-Pad59)") (class "Default")
      (node (ref "U1") (pin "59") (pinfunction "P2[18]_59") (pintype "passive"))
    )
    (net (code "130") (name "unconnected-(U1C-P2[19]-Pad67)") (class "Default")
      (node (ref "U1") (pin "67") (pinfunction "P2[19]_67") (pintype "passive"))
    )
    (net (code "131") (name "unconnected-(U1C-P2[20]-Pad73)") (class "Default")
      (node (ref "U1") (pin "73") (pinfunction "P2[20]_73") (pintype "passive"))
    )
    (net (code "132") (name "unconnected-(U1C-P2[22]-Pad85)") (class "Default")
      (node (ref "U1") (pin "85") (pinfunction "P2[22]_85") (pintype "passive"))
    )
    (net (code "133") (name "unconnected-(U1C-P2[23]-Pad64)") (class "Default")
      (node (ref "U1") (pin "64") (pinfunction "P2[23]_64") (pintype "passive"))
    )
    (net (code "134") (name "unconnected-(U1C-P2[26]-Pad57)") (class "Default")
      (node (ref "U1") (pin "57") (pinfunction "P2[26]_57") (pintype "passive"))
    )
    (net (code "135") (name "unconnected-(U1C-P2[27]-Pad47)") (class "Default")
      (node (ref "U1") (pin "47") (pinfunction "P2[27]_47") (pintype "passive"))
    )
    (net (code "136") (name "unconnected-(U1C-P2[28]-Pad49)") (class "Default")
      (node (ref "U1") (pin "49") (pinfunction "P2[28]_49") (pintype "passive"))
    )
    (net (code "137") (name "unconnected-(U1C-P2[29]-Pad43)") (class "Default")
      (node (ref "U1") (pin "43") (pinfunction "P2[29]_43") (pintype "passive"))
    )
    (net (code "138") (name "unconnected-(U1C-P2[30]-Pad31)") (class "Default")
      (node (ref "U1") (pin "31") (pinfunction "P2[30]_31") (pintype "passive"))
    )
    (net (code "139") (name "unconnected-(U1C-P2[31]-Pad39)") (class "Default")
      (node (ref "U1") (pin "39") (pinfunction "P2[31]_39") (pintype "passive"))
    )
    (net (code "140") (name "unconnected-(U1D-P3[0]-Pad197)") (class "Default")
      (node (ref "U1") (pin "197") (pinfunction "P3[0]_197") (pintype "passive"))
    )
    (net (code "141") (name "unconnected-(U1D-P3[1]-Pad201)") (class "Default")
      (node (ref "U1") (pin "201") (pinfunction "P3[1]_201") (pintype "passive"))
    )
    (net (code "142") (name "unconnected-(U1D-P3[2]-Pad207)") (class "Default")
      (node (ref "U1") (pin "207") (pinfunction "P3[2]_207") (pintype "passive"))
    )
    (net (code "143") (name "unconnected-(U1D-P3[3]-Pad3)") (class "Default")
      (node (ref "U1") (pin "3") (pinfunction "P3[3]_3") (pintype "passive"))
    )
    (net (code "144") (name "unconnected-(U1D-P3[4]-Pad13)") (class "Default")
      (node (ref "U1") (pin "13") (pinfunction "P3[4]_13") (pintype "passive"))
    )
    (net (code "145") (name "unconnected-(U1D-P3[5]-Pad17)") (class "Default")
      (node (ref "U1") (pin "17") (pinfunction "P3[5]_17") (pintype "passive"))
    )
    (net (code "146") (name "unconnected-(U1D-P3[6]-Pad23)") (class "Default")
      (node (ref "U1") (pin "23") (pinfunction "P3[6]_23") (pintype "passive"))
    )
    (net (code "147") (name "unconnected-(U1D-P3[7]-Pad27)") (class "Default")
      (node (ref "U1") (pin "27") (pinfunction "P3[7]_27") (pintype "passive"))
    )
    (net (code "148") (name "unconnected-(U1D-P3[8]-Pad191)") (class "Default")
      (node (ref "U1") (pin "191") (pinfunction "P3[8]_191") (pintype "passive"))
    )
    (net (code "149") (name "unconnected-(U1D-P3[9]-Pad199)") (class "Default")
      (node (ref "U1") (pin "199") (pinfunction "P3[9]_199") (pintype "passive"))
    )
    (net (code "150") (name "unconnected-(U1D-P3[10]-Pad205)") (class "Default")
      (node (ref "U1") (pin "205") (pinfunction "P3[10]_205") (pintype "passive"))
    )
    (net (code "151") (name "unconnected-(U1D-P3[11]-Pad208)") (class "Default")
      (node (ref "U1") (pin "208") (pinfunction "P3[11]_208") (pintype "passive"))
    )
    (net (code "152") (name "unconnected-(U1D-P3[12]-Pad1)") (class "Default")
      (node (ref "U1") (pin "1") (pinfunction "P3[12]_1") (pintype "passive"))
    )
    (net (code "153") (name "unconnected-(U1D-P3[13]-Pad7)") (class "Default")
      (node (ref "U1") (pin "7") (pinfunction "P3[13]_7") (pintype "passive"))
    )
    (net (code "154") (name "unconnected-(U1D-P3[14]-Pad21)") (class "Default")
      (node (ref "U1") (pin "21") (pinfunction "P3[14]_21") (pintype "passive"))
    )
    (net (code "155") (name "unconnected-(U1D-P3[15]-Pad28)") (class "Default")
      (node (ref "U1") (pin "28") (pinfunction "P3[15]_28") (pintype "passive"))
    )
    (net (code "156") (name "unconnected-(U1D-P3[17]-Pad143)") (class "Default")
      (node (ref "U1") (pin "143") (pinfunction "P3[17]_143") (pintype "passive"))
    )
    (net (code "157") (name "unconnected-(U1D-P3[18]-Pad151)") (class "Default")
      (node (ref "U1") (pin "151") (pinfunction "P3[18]_151") (pintype "passive"))
    )
    (net (code "158") (name "unconnected-(U1D-P3[20]-Pad167)") (class "Default")
      (node (ref "U1") (pin "167") (pinfunction "P3[20]_167") (pintype "passive"))
    )
    (net (code "159") (name "unconnected-(U1D-P3[22]-Pad195)") (class "Default")
      (node (ref "U1") (pin "195") (pinfunction "P3[22]_195") (pintype "passive"))
    )
    (net (code "160") (name "unconnected-(U1D-P3[23]-Pad65)") (class "Default")
      (node (ref "U1") (pin "65") (pinfunction "P3[23]_65") (pintype "passive"))
    )
    (net (code "161") (name "unconnected-(U1D-P3[24]-Pad58)") (class "Default")
      (node (ref "U1") (pin "58") (pinfunction "P3[24]_58") (pintype "passive"))
    )
    (net (code "162") (name "unconnected-(U1D-P3[27]-Pad203)") (class "Default")
      (node (ref "U1") (pin "203") (pinfunction "P3[27]_203") (pintype "passive"))
    )
    (net (code "163") (name "unconnected-(U1D-P3[28]-Pad5)") (class "Default")
      (node (ref "U1") (pin "5") (pinfunction "P3[28]_5") (pintype "passive"))
    )
    (net (code "164") (name "unconnected-(U1D-P3[29]-Pad11)") (class "Default")
      (node (ref "U1") (pin "11") (pinfunction "P3[29]_11") (pintype "passive"))
    )
    (net (code "165") (name "unconnected-(U1D-P3[30]-Pad19)") (class "Default")
      (node (ref "U1") (pin "19") (pinfunction "P3[30]_19") (pintype "passive"))
    )
    (net (code "166") (name "unconnected-(U1D-P3[31]-Pad25)") (class "Default")
      (node (ref "U1") (pin "25") (pinfunction "P3[31]_25") (pintype "passive"))
    )
    (net (code "167") (name "unconnected-(U1E-P4[0]-Pad75)") (class "Default")
      (node (ref "U1") (pin "75") (pinfunction "P4[0]_75") (pintype "passive"))
    )
    (net (code "168") (name "unconnected-(U1E-P4[6]-Pad113)") (class "Default")
      (node (ref "U1") (pin "113") (pinfunction "P4[6]_113") (pintype "passive"))
    )
    (net (code "169") (name "unconnected-(U1E-P4[7]-Pad121)") (class "Default")
      (node (ref "U1") (pin "121") (pinfunction "P4[7]_121") (pintype "passive"))
    )
    (net (code "170") (name "unconnected-(U1E-P4[9]-Pad131)") (class "Default")
      (node (ref "U1") (pin "131") (pinfunction "P4[9]_131") (pintype "passive"))
    )
    (net (code "171") (name "unconnected-(U1E-P4[11]-Pad145)") (class "Default")
      (node (ref "U1") (pin "145") (pinfunction "P4[11]_145") (pintype "passive"))
    )
    (net (code "172") (name "unconnected-(U1E-P4[12]-Pad149)") (class "Default")
      (node (ref "U1") (pin "149") (pinfunction "P4[12]_149") (pintype "passive"))
    )
    (net (code "173") (name "unconnected-(U1E-P4[13]-Pad155)") (class "Default")
      (node (ref "U1") (pin "155") (pinfunction "P4[13]_155") (pintype "passive"))
    )
    (net (code "174") (name "unconnected-(U1E-P4[19]-Pad111)") (class "Default")
      (node (ref "U1") (pin "111") (pinfunction "P4[19]_111") (pintype "passive"))
    )
    (net (code "175") (name "unconnected-(U1E-P4[21]-Pad115)") (class "Default")
      (node (ref "U1") (pin "115") (pinfunction "P4[21]_115") (pintype "passive"))
    )
    (net (code "176") (name "unconnected-(U1E-P4[22]-Pad123)") (class "Default")
      (node (ref "U1") (pin "123") (pinfunction "P4[22]_123") (pintype "passive"))
    )
    (net (code "177") (name "unconnected-(U1E-P4[24]-Pad183)") (class "Default")
      (node (ref "U1") (pin "183") (pinfunction "P4[24]_183") (pintype "passive"))
    )
    (net (code "178") (name "unconnected-(U1E-P4[25]-Pad179)") (class "Default")
      (node (ref "U1") (pin "179") (pinfunction "P4[25]_179") (pintype "passive"))
    )
    (net (code "179") (name "unconnected-(U1E-P4[26]-Pad119)") (class "Default")
      (node (ref "U1") (pin "119") (pinfunction "P4[26]_119") (pintype "passive"))
    )
    (net (code "180") (name "unconnected-(U1E-P4[29]-Pad176)") (class "Default")
      (node (ref "U1") (pin "176") (pinfunction "P4[29]_176") (pintype "passive"))
    )
    (net (code "181") (name "unconnected-(U1E-P4[30]-Pad187)") (class "Default")
      (node (ref "U1") (pin "187") (pinfunction "P4[30]_187") (pintype "passive"))
    )
    (net (code "182") (name "unconnected-(U1E-P4[31]-Pad193)") (class "Default")
      (node (ref "U1") (pin "193") (pinfunction "P4[31]_193") (pintype "passive"))
    )
    (net (code "183") (name "unconnected-(U1F-P5[0]-Pad9)") (class "Default")
      (node (ref "U1") (pin "9") (pinfunction "P5[0]_9") (pintype "passive+no_connect"))
    )
    (net (code "184") (name "unconnected-(U1F-P5[1]-Pad30)") (class "Default")
      (node (ref "U1") (pin "30") (pinfunction "P5[1]_30") (pintype "passive+no_connect"))
    )
    (net (code "185") (name "unconnected-(U1F-P5[2]-Pad117)") (class "Default")
      (node (ref "U1") (pin "117") (pinfunction "P5[2]_117") (pintype "passive+no_connect"))
    )
    (net (code "186") (name "unconnected-(U1F-P5[3]-Pad141)") (class "Default")
      (node (ref "U1") (pin "141") (pinfunction "P5[3]_141") (pintype "passive+no_connect"))
    )
    (net (code "187") (name "unconnected-(U1F-P5[4]-Pad206)") (class "Default")
      (node (ref "U1") (pin "206") (pinfunction "P5[4]_206") (pintype "passive+no_connect"))
    )
    (net (code "188") (name "unconnected-(U1G-JTAG_~{TRST}-Pad8)") (class "Default")
      (node (ref "U1") (pin "8") (pinfunction "JTAG_~{TRST}_8") (pintype "passive+no_connect"))
    )
    (net (code "189") (name "unconnected-(U1G-RTCX1-Pad34)") (class "Default")
      (node (ref "U1") (pin "34") (pinfunction "RTCX1_34") (pintype "passive+no_connect"))
    )
    (net (code "190") (name "unconnected-(U1G-RTCX2-Pad36)") (class "Default")
      (node (ref "U1") (pin "36") (pinfunction "RTCX2_36") (pintype "passive+no_connect"))
    )
    (net (code "191") (name "unconnected-(U1G-RTC_ALARM-Pad37)") (class "Default")
      (node (ref "U1") (pin "37") (pinfunction "RTC_ALARM_37") (pintype "passive+no_connect"))
    )
    (net (code "192") (name "unconnected-(U1G-USB_D-2-Pad52)") (class "Default")
      (node (ref "U1") (pin "52") (pinfunction "USB_D-2_52") (pintype "passive+no_connect"))
    )
    (net (code "193") (name "unconnected-(U1G-~{RSTOUT}-Pad29)") (class "Default")
      (node (ref "U1") (pin "29") (pinfunction "~{RSTOUT}_29") (pintype "passive+no_connect"))
    )
  )
)
